# raspi3_nonHat.net
KiCad netlist of a schematic drawn in EAGLE
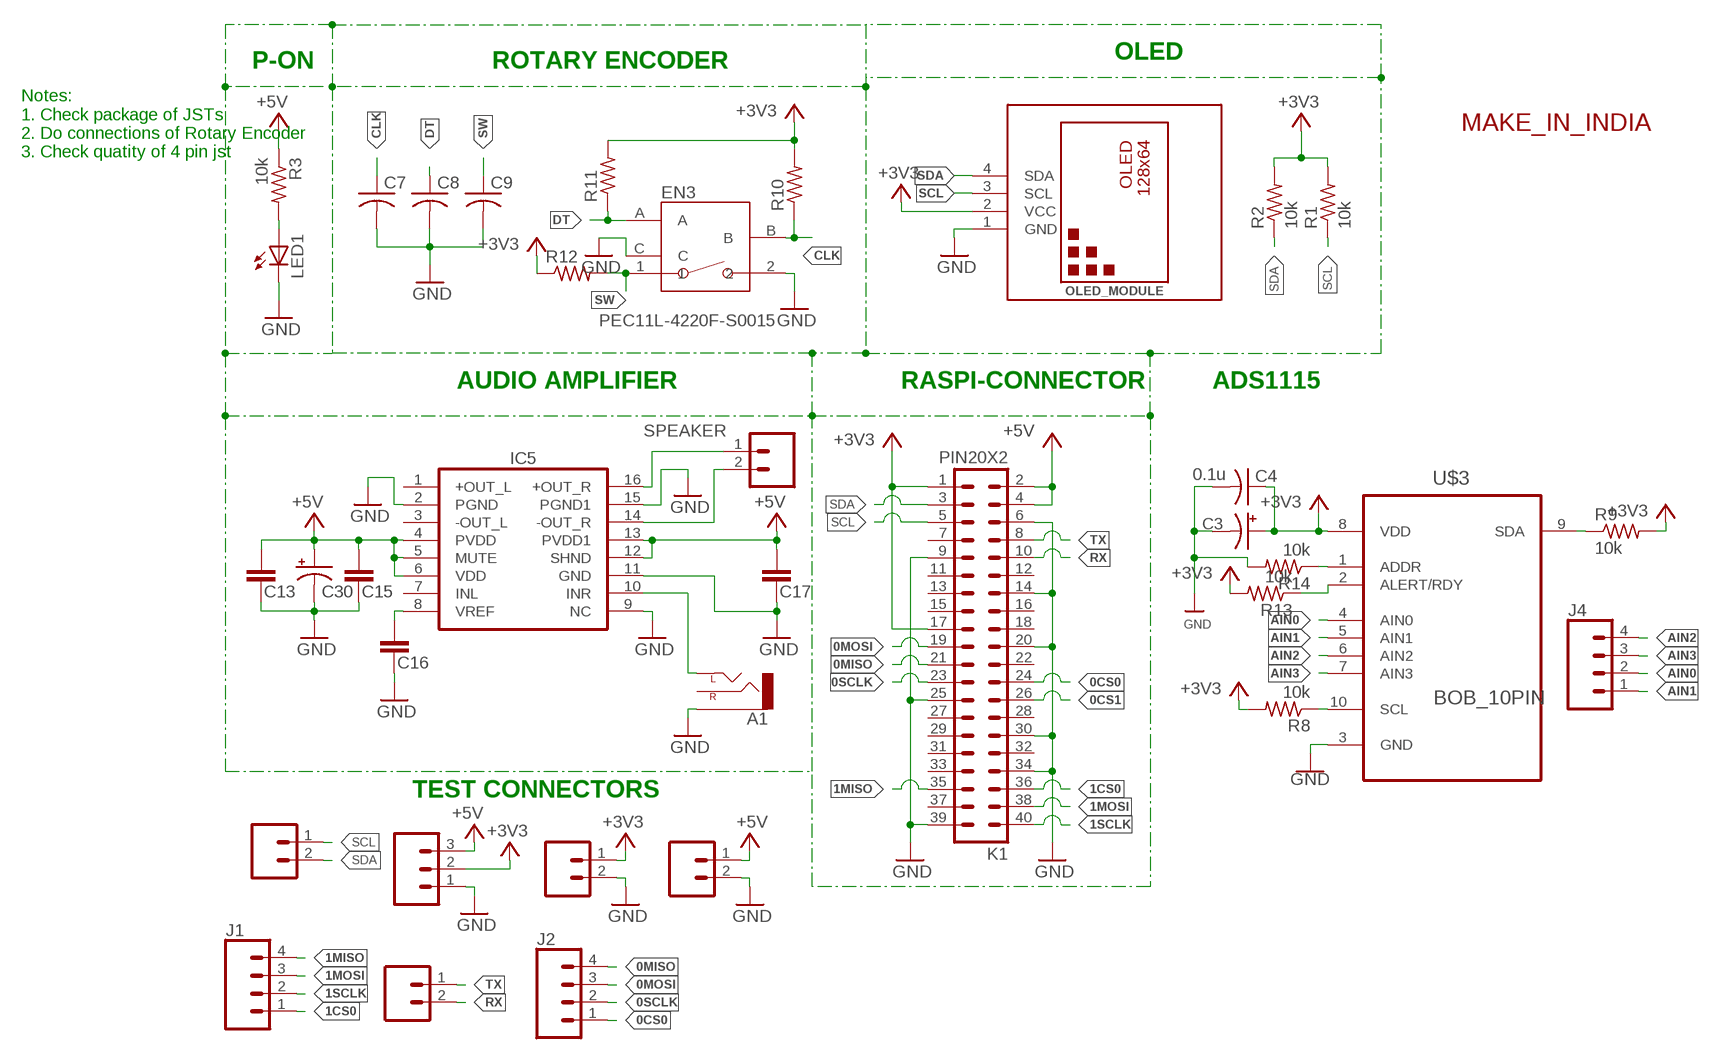
[diagram p0: schematic, sheet 1]

(export (version "E")
  (design (tool "Eeschema 10.0.6"))
  (components
    (comp (ref "A1")
      (value "AUDIO-JACKPTH")
      (footprint "eagle-import:AUDIO-JACK")
      (libsource (lib "eagle-import") (part "AUDIO-JACKPTH"))
    )
    (comp (ref "C3")
      (value "10u")
      (footprint "eagle-import:C_6032-28R")
      (libsource (lib "eagle-import") (part "CAP_POL_10V"))
    )
    (comp (ref "C4")
      (value "0.1u")
      (footprint "eagle-import:C0805")
      (libsource (lib "eagle-import") (part "CAP0805"))
    )
    (comp (ref "C7")
      (value "C-USC0603K")
      (footprint "eagle-import:C0603K")
      (libsource (lib "eagle-import") (part "C-USC0603K"))
    )
    (comp (ref "C8")
      (value "C-USC0603K")
      (footprint "eagle-import:C0603K")
      (libsource (lib "eagle-import") (part "C-USC0603K"))
    )
    (comp (ref "C9")
      (value "C-USC0603K")
      (footprint "eagle-import:C0603K")
      (libsource (lib "eagle-import") (part "C-USC0603K"))
    )
    (comp (ref "C13")
      (value "1uf")
      (footprint "eagle-import:C1206")
      (libsource (lib "eagle-import") (part "C-EUC1206"))
    )
    (comp (ref "C15")
      (value "1uf")
      (footprint "eagle-import:C1206")
      (libsource (lib "eagle-import") (part "C-EUC1206"))
    )
    (comp (ref "C16")
      (value "0.1uf")
      (footprint "eagle-import:C1206")
      (libsource (lib "eagle-import") (part "C-EUC1206"))
    )
    (comp (ref "C17")
      (value "1uf")
      (footprint "eagle-import:C1206")
      (libsource (lib "eagle-import") (part "C-EUC1206"))
    )
    (comp (ref "C30")
      (value "CAP_POL_10V")
      (footprint "eagle-import:C_6032-28R")
      (libsource (lib "eagle-import") (part "CEDT_SEPTEMBER_V2_CAP_POL_10V"))
    )
    (comp (ref "EN3")
      (value "PEC11L-4220F-S0015")
      (footprint "eagle-import:PEC11L-4220F-S0015")
      (fields
        (field (name "DIGIKEY_PARTNO") "PEC11L-4220F-S0015-ND")
        (field (name "MANUFACTURER") "Bourns Inc.")
        (field (name "CREATED_BY") "PCBLayout.com")
      )
      (libsource (lib "eagle-import") (part "PEC11L-4220F-S0015"))
    )
    (comp (ref "IC5")
      (value "PAM8403")
      (footprint "eagle-import:SOP-16")
      (libsource (lib "eagle-import") (part "PAM8403"))
    )
    (comp (ref "J1")
      (value "CONN_04POLAR")
      (footprint "eagle-import:MOLEX-1X4")
      (libsource (lib "eagle-import") (part "CONN_04POLAR"))
    )
    (comp (ref "J2")
      (value "CONN_04POLAR")
      (footprint "eagle-import:MOLEX-1X4")
      (libsource (lib "eagle-import") (part "CONN_04POLAR"))
    )
    (comp (ref "J4")
      (value "CONN_04POLAR")
      (footprint "eagle-import:MOLEX-1X4")
      (libsource (lib "eagle-import") (part "CONN_04POLAR"))
    )
    (comp (ref "K1")
      (value "PIN20X2")
      (footprint "eagle-import:PIN_20X2")
      (libsource (lib "eagle-import") (part "PIN20X2"))
    )
    (comp (ref "LED1")
      (value "LED3MM")
      (footprint "eagle-import:LED3MM")
      (libsource (lib "eagle-import") (part "LED3MM"))
    )
    (comp (ref "OLED_MODULE")
      (value "DIY-MODULES_DISPLAY-OLED-128X64-I2C")
      (footprint "eagle-import:DIY-MODULES_DISPLAY-OLED-128X64-I2C")
      (libsource (lib "eagle-import") (part "DIY-MODULES_DISPLAY-OLED-128X64-I2C"))
    )
    (comp (ref "POWER")
      (value "CONN_03POLAR")
      (footprint "eagle-import:MOLEX-1X3")
      (libsource (lib "eagle-import") (part "CONN_03POLAR"))
    )
    (comp (ref "R1")
      (value "10k")
      (footprint "eagle-import:0207_7")
      (libsource (lib "eagle-import") (part "RESISTOR0207/7"))
    )
    (comp (ref "R2")
      (value "10k")
      (footprint "eagle-import:0207_7")
      (libsource (lib "eagle-import") (part "RESISTOR0207/7"))
    )
    (comp (ref "R3")
      (value "10k")
      (footprint "eagle-import:0207_7")
      (libsource (lib "eagle-import") (part "RESISTOR0207/7"))
    )
    (comp (ref "R8")
      (value "10k")
      (footprint "eagle-import:R0603")
      (libsource (lib "eagle-import") (part "CEDT_JANUARY_2015_v5_RESISTOR0603"))
    )
    (comp (ref "R9")
      (value "10k")
      (footprint "eagle-import:R0603")
      (libsource (lib "eagle-import") (part "CEDT_JANUARY_2015_v5_RESISTOR0603"))
    )
    (comp (ref "R10")
      (value "R-US_M0805")
      (footprint "eagle-import:M0805")
      (libsource (lib "eagle-import") (part "R-US_M0805"))
    )
    (comp (ref "R11")
      (value "R-US_M0805")
      (footprint "eagle-import:M0805")
      (libsource (lib "eagle-import") (part "R-US_M0805"))
    )
    (comp (ref "R12")
      (value "R-US_M0805")
      (footprint "eagle-import:M0805")
      (libsource (lib "eagle-import") (part "R-US_M0805"))
    )
    (comp (ref "R13")
      (value "10k")
      (footprint "eagle-import:R0603")
      (libsource (lib "eagle-import") (part "CEDT_JANUARY_2015_v5_RESISTOR0603"))
    )
    (comp (ref "R14")
      (value "10k")
      (footprint "eagle-import:R0603")
      (libsource (lib "eagle-import") (part "CEDT_JANUARY_2015_v5_RESISTOR0603"))
    )
    (comp (ref "SPEAKER")
      (value "M02")
      (footprint "eagle-import:02P")
      (libsource (lib "eagle-import") (part "M02"))
    )
    (comp (ref "THERMISTOR1")
      (value "CONN_02POLAR")
      (footprint "eagle-import:MOLEX-1X2")
      (libsource (lib "eagle-import") (part "CONN_02POLAR"))
    )
    (comp (ref "THERMISTOR2")
      (value "CONN_02POLAR")
      (footprint "eagle-import:MOLEX-1X2")
      (libsource (lib "eagle-import") (part "CONN_02POLAR"))
    )
    (comp (ref "THERMISTOR3")
      (value "CONN_02POLAR")
      (footprint "eagle-import:MOLEX-1X2")
      (libsource (lib "eagle-import") (part "CONN_02POLAR"))
    )
    (comp (ref "THERMISTOR4")
      (value "CONN_02POLAR")
      (footprint "eagle-import:MOLEX-1X2")
      (libsource (lib "eagle-import") (part "CONN_02POLAR"))
    )
    (comp (ref "U$1")
      (value "MAKE-IN-INDIA-LOGO")
      (footprint "eagle-import:MAKE-IN-INDIA")
      (libsource (lib "eagle-import") (part "MAKE-IN-INDIA-LOGO"))
    )
    (comp (ref "U$3")
      (value "BOB_10PIN")
      (footprint "eagle-import:BOB10")
      (libsource (lib "eagle-import") (part "BOB_10PIN"))
    )
  )
  (nets
    (net (code "1") (name "+3V3") (class "Default")
      (node (ref "C3") (pin "+") (pinfunction "+_+") (pintype "passive"))
      (node (ref "C4") (pin "1") (pinfunction "1_1") (pintype "passive"))
      (node (ref "K1") (pin "1") (pinfunction "1_1") (pintype "passive"))
      (node (ref "K1") (pin "17") (pinfunction "17_17") (pintype "passive"))
      (node (ref "OLED_MODULE") (pin "2") (pinfunction "VCC_2") (pintype "power_in"))
      (node (ref "POWER") (pin "2") (pinfunction "2_2") (pintype "passive"))
      (node (ref "R1") (pin "2") (pinfunction "2_2") (pintype "passive"))
      (node (ref "R10") (pin "2") (pinfunction "2_2") (pintype "passive"))
      (node (ref "R11") (pin "2") (pinfunction "2_2") (pintype "passive"))
      (node (ref "R12") (pin "1") (pinfunction "1_1") (pintype "passive"))
      (node (ref "R13") (pin "2") (pinfunction "2_2") (pintype "passive"))
      (node (ref "R2") (pin "2") (pinfunction "2_2") (pintype "passive"))
      (node (ref "R8") (pin "2") (pinfunction "2_2") (pintype "passive"))
      (node (ref "R9") (pin "2") (pinfunction "2_2") (pintype "passive"))
      (node (ref "THERMISTOR2") (pin "1") (pinfunction "1_1") (pintype "passive"))
      (node (ref "U$3") (pin "8") (pinfunction "VDD_8") (pintype "power_in"))
    )
    (net (code "2") (name "+5V") (class "Default")
      (node (ref "C13") (pin "1") (pinfunction "1_1") (pintype "passive"))
      (node (ref "C15") (pin "2") (pinfunction "2_2") (pintype "passive"))
      (node (ref "C17") (pin "2") (pinfunction "2_2") (pintype "passive"))
      (node (ref "C30") (pin "+") (pinfunction "+_+") (pintype "passive"))
      (node (ref "IC5") (pin "12") (pinfunction "SHND_12") (pintype "output"))
      (node (ref "IC5") (pin "13") (pinfunction "PVDD1_13") (pintype "output"))
      (node (ref "IC5") (pin "4") (pinfunction "PVDD_4") (pintype "input"))
      (node (ref "IC5") (pin "5") (pinfunction "MUTE_5") (pintype "input"))
      (node (ref "IC5") (pin "6") (pinfunction "VDD_6") (pintype "input"))
      (node (ref "K1") (pin "2") (pinfunction "2_2") (pintype "passive"))
      (node (ref "K1") (pin "4") (pinfunction "4_4") (pintype "passive"))
      (node (ref "POWER") (pin "3") (pinfunction "3_3") (pintype "passive"))
      (node (ref "R3") (pin "1") (pinfunction "1_1") (pintype "passive"))
      (node (ref "THERMISTOR3") (pin "1") (pinfunction "1_1") (pintype "passive"))
    )
    (net (code "3") (name "0CS0") (class "Default")
      (node (ref "J2") (pin "1") (pinfunction "1_1") (pintype "passive"))
      (node (ref "K1") (pin "24") (pinfunction "24_24") (pintype "passive"))
    )
    (net (code "4") (name "0CS1") (class "Default")
      (node (ref "K1") (pin "26") (pinfunction "26_26") (pintype "passive"))
    )
    (net (code "5") (name "0MISO") (class "Default")
      (node (ref "J2") (pin "4") (pinfunction "4_4") (pintype "passive"))
      (node (ref "K1") (pin "21") (pinfunction "21_21") (pintype "passive"))
    )
    (net (code "6") (name "0MOSI") (class "Default")
      (node (ref "J2") (pin "3") (pinfunction "3_3") (pintype "passive"))
      (node (ref "K1") (pin "19") (pinfunction "19_19") (pintype "passive"))
    )
    (net (code "7") (name "0SCLK") (class "Default")
      (node (ref "J2") (pin "2") (pinfunction "2_2") (pintype "passive"))
      (node (ref "K1") (pin "23") (pinfunction "23_23") (pintype "passive"))
    )
    (net (code "8") (name "1CS0") (class "Default")
      (node (ref "J1") (pin "1") (pinfunction "1_1") (pintype "passive"))
      (node (ref "K1") (pin "36") (pinfunction "36_36") (pintype "passive"))
    )
    (net (code "9") (name "1MISO") (class "Default")
      (node (ref "J1") (pin "4") (pinfunction "4_4") (pintype "passive"))
      (node (ref "K1") (pin "35") (pinfunction "35_35") (pintype "passive"))
    )
    (net (code "10") (name "1MOSI") (class "Default")
      (node (ref "J1") (pin "3") (pinfunction "3_3") (pintype "passive"))
      (node (ref "K1") (pin "38") (pinfunction "38_38") (pintype "passive"))
    )
    (net (code "11") (name "1SCLK") (class "Default")
      (node (ref "J1") (pin "2") (pinfunction "2_2") (pintype "passive"))
      (node (ref "K1") (pin "40") (pinfunction "40_40") (pintype "passive"))
    )
    (net (code "12") (name "AIN0") (class "Default")
      (node (ref "J4") (pin "2") (pinfunction "2_2") (pintype "passive"))
      (node (ref "U$3") (pin "4") (pinfunction "AIN0_4") (pintype "input"))
    )
    (net (code "13") (name "AIN1") (class "Default")
      (node (ref "J4") (pin "1") (pinfunction "1_1") (pintype "passive"))
      (node (ref "U$3") (pin "5") (pinfunction "AIN1_5") (pintype "input"))
    )
    (net (code "14") (name "AIN2") (class "Default")
      (node (ref "J4") (pin "4") (pinfunction "4_4") (pintype "passive"))
      (node (ref "U$3") (pin "6") (pinfunction "AIN2_6") (pintype "input"))
    )
    (net (code "15") (name "AIN3") (class "Default")
      (node (ref "J4") (pin "3") (pinfunction "3_3") (pintype "passive"))
      (node (ref "U$3") (pin "7") (pinfunction "AIN3_7") (pintype "input"))
    )
    (net (code "16") (name "CLK") (class "Default")
      (node (ref "C7") (pin "1") (pinfunction "1_1") (pintype "passive"))
      (node (ref "EN3") (pin "B") (pinfunction "B_B") (pintype "passive"))
      (node (ref "R10") (pin "1") (pinfunction "1_1") (pintype "passive"))
    )
    (net (code "17") (name "DT") (class "Default")
      (node (ref "C8") (pin "1") (pinfunction "1_1") (pintype "passive"))
      (node (ref "EN3") (pin "A") (pinfunction "A_A") (pintype "passive"))
      (node (ref "R11") (pin "1") (pinfunction "1_1") (pintype "passive"))
    )
    (net (code "18") (name "GND") (class "Default")
      (node (ref "A1") (pin "SLEEVE") (pinfunction "SLEEVE_SLEEVE") (pintype "bidirectional"))
      (node (ref "C13") (pin "2") (pinfunction "2_2") (pintype "passive"))
      (node (ref "C15") (pin "1") (pinfunction "1_1") (pintype "passive"))
      (node (ref "C16") (pin "2") (pinfunction "2_2") (pintype "passive"))
      (node (ref "C17") (pin "1") (pinfunction "1_1") (pintype "passive"))
      (node (ref "C3") (pin "-") (pinfunction "-_-") (pintype "passive"))
      (node (ref "C30") (pin "-") (pinfunction "-_-") (pintype "passive"))
      (node (ref "C4") (pin "2") (pinfunction "2_2") (pintype "passive"))
      (node (ref "C7") (pin "2") (pinfunction "2_2") (pintype "passive"))
      (node (ref "C8") (pin "2") (pinfunction "2_2") (pintype "passive"))
      (node (ref "C9") (pin "2") (pinfunction "2_2") (pintype "passive"))
      (node (ref "EN3") (pin "2") (pinfunction "2_2") (pintype "passive"))
      (node (ref "EN3") (pin "C") (pinfunction "C_C") (pintype "passive"))
      (node (ref "IC5") (pin "11") (pinfunction "GND_11") (pintype "output"))
      (node (ref "IC5") (pin "15") (pinfunction "PGND1_15") (pintype "output"))
      (node (ref "IC5") (pin "2") (pinfunction "PGND_2") (pintype "input"))
      (node (ref "IC5") (pin "9") (pinfunction "NC_9") (pintype "output"))
      (node (ref "K1") (pin "14") (pinfunction "14_14") (pintype "passive"))
      (node (ref "K1") (pin "20") (pinfunction "20_20") (pintype "passive"))
      (node (ref "K1") (pin "25") (pinfunction "25_25") (pintype "passive"))
      (node (ref "K1") (pin "30") (pinfunction "30_30") (pintype "passive"))
      (node (ref "K1") (pin "34") (pinfunction "34_34") (pintype "passive"))
      (node (ref "K1") (pin "39") (pinfunction "39_39") (pintype "passive"))
      (node (ref "K1") (pin "6") (pinfunction "6_6") (pintype "passive"))
      (node (ref "K1") (pin "9") (pinfunction "9_9") (pintype "passive"))
      (node (ref "LED1") (pin "K") (pinfunction "C_K") (pintype "passive"))
      (node (ref "OLED_MODULE") (pin "1") (pinfunction "GND_1") (pintype "power_in"))
      (node (ref "POWER") (pin "1") (pinfunction "1_1") (pintype "passive"))
      (node (ref "R14") (pin "2") (pinfunction "2_2") (pintype "passive"))
      (node (ref "THERMISTOR2") (pin "2") (pinfunction "2_2") (pintype "passive"))
      (node (ref "THERMISTOR3") (pin "2") (pinfunction "2_2") (pintype "passive"))
      (node (ref "U$3") (pin "3") (pinfunction "GND_3") (pintype "passive"))
    )
    (net (code "19") (name "Net-(A1-LEFT)") (class "Default")
      (node (ref "A1") (pin "TIP") (pinfunction "LEFT_TIP") (pintype "bidirectional"))
      (node (ref "IC5") (pin "10") (pinfunction "INR_10") (pintype "output"))
    )
    (net (code "20") (name "Net-(IC5-+OUT_R)") (class "Default")
      (node (ref "IC5") (pin "16") (pinfunction "+OUT_R_16") (pintype "output"))
      (node (ref "SPEAKER") (pin "1") (pinfunction "1_1") (pintype "passive"))
    )
    (net (code "21") (name "Net-(IC5--OUT_R)") (class "Default")
      (node (ref "IC5") (pin "14") (pinfunction "-OUT_R_14") (pintype "output"))
      (node (ref "SPEAKER") (pin "2") (pinfunction "2_2") (pintype "passive"))
    )
    (net (code "22") (name "Net-(IC5-VREF)") (class "Default")
      (node (ref "C16") (pin "1") (pinfunction "1_1") (pintype "passive"))
      (node (ref "IC5") (pin "8") (pinfunction "VREF_8") (pintype "input"))
    )
    (net (code "23") (name "Net-(LED1-PadA)") (class "Default")
      (node (ref "LED1") (pin "A") (pinfunction "A_A") (pintype "passive"))
      (node (ref "R3") (pin "2") (pinfunction "2_2") (pintype "passive"))
    )
    (net (code "24") (name "Net-(U$3-ADDR)") (class "Default")
      (node (ref "R14") (pin "1") (pinfunction "1_1") (pintype "passive"))
      (node (ref "U$3") (pin "1") (pinfunction "ADDR_1") (pintype "input"))
    )
    (net (code "25") (name "Net-(U$3-ALERT{slash}RDY)") (class "Default")
      (node (ref "R13") (pin "1") (pinfunction "1_1") (pintype "passive"))
      (node (ref "U$3") (pin "2") (pinfunction "ALERT/RDY_2") (pintype "input"))
    )
    (net (code "26") (name "Net-(U$3-SCL)") (class "Default")
      (node (ref "R8") (pin "1") (pinfunction "1_1") (pintype "passive"))
      (node (ref "U$3") (pin "10") (pinfunction "SCL_10") (pintype "input"))
    )
    (net (code "27") (name "Net-(U$3-SDA)") (class "Default")
      (node (ref "R9") (pin "1") (pinfunction "1_1") (pintype "passive"))
      (node (ref "U$3") (pin "9") (pinfunction "SDA_9") (pintype "bidirectional"))
    )
    (net (code "28") (name "RX") (class "Default")
      (node (ref "K1") (pin "10") (pinfunction "10_10") (pintype "passive"))
      (node (ref "THERMISTOR4") (pin "2") (pinfunction "2_2") (pintype "passive"))
    )
    (net (code "29") (name "SCL") (class "Default")
      (node (ref "K1") (pin "5") (pinfunction "5_5") (pintype "passive"))
      (node (ref "OLED_MODULE") (pin "3") (pinfunction "SCL_3") (pintype "bidirectional"))
      (node (ref "R1") (pin "1") (pinfunction "1_1") (pintype "passive"))
      (node (ref "THERMISTOR1") (pin "1") (pinfunction "1_1") (pintype "passive"))
    )
    (net (code "30") (name "SDA") (class "Default")
      (node (ref "K1") (pin "3") (pinfunction "3_3") (pintype "passive"))
      (node (ref "OLED_MODULE") (pin "4") (pinfunction "SDA_4") (pintype "bidirectional"))
      (node (ref "R2") (pin "1") (pinfunction "1_1") (pintype "passive"))
      (node (ref "THERMISTOR1") (pin "2") (pinfunction "2_2") (pintype "passive"))
    )
    (net (code "31") (name "SW") (class "Default")
      (node (ref "C9") (pin "1") (pinfunction "1_1") (pintype "passive"))
      (node (ref "EN3") (pin "1") (pinfunction "1_1") (pintype "passive"))
      (node (ref "R12") (pin "2") (pinfunction "2_2") (pintype "passive"))
    )
    (net (code "32") (name "TX") (class "Default")
      (node (ref "K1") (pin "8") (pinfunction "8_8") (pintype "passive"))
      (node (ref "THERMISTOR4") (pin "1") (pinfunction "1_1") (pintype "passive"))
    )
    (net (code "33") (name "unconnected-(A1-RIGHT-PadRING)") (class "Default")
      (node (ref "A1") (pin "RING") (pinfunction "RIGHT_RING") (pintype "bidirectional"))
    )
    (net (code "34") (name "unconnected-(IC5-+OUT_L-Pad1)") (class "Default")
      (node (ref "IC5") (pin "1") (pinfunction "+OUT_L_1") (pintype "input"))
    )
    (net (code "35") (name "unconnected-(IC5--OUT_L-Pad3)") (class "Default")
      (node (ref "IC5") (pin "3") (pinfunction "-OUT_L_3") (pintype "input"))
    )
    (net (code "36") (name "unconnected-(IC5-INL-Pad7)") (class "Default")
      (node (ref "IC5") (pin "7") (pinfunction "INL_7") (pintype "input"))
    )
    (net (code "37") (name "unconnected-(K1-Pad7)") (class "Default")
      (node (ref "K1") (pin "7") (pinfunction "7_7") (pintype "passive"))
    )
    (net (code "38") (name "unconnected-(K1-Pad11)") (class "Default")
      (node (ref "K1") (pin "11") (pinfunction "11_11") (pintype "passive"))
    )
    (net (code "39") (name "unconnected-(K1-Pad12)") (class "Default")
      (node (ref "K1") (pin "12") (pinfunction "12_12") (pintype "passive"))
    )
    (net (code "40") (name "unconnected-(K1-Pad13)") (class "Default")
      (node (ref "K1") (pin "13") (pinfunction "13_13") (pintype "passive"))
    )
    (net (code "41") (name "unconnected-(K1-Pad15)") (class "Default")
      (node (ref "K1") (pin "15") (pinfunction "15_15") (pintype "passive"))
    )
    (net (code "42") (name "unconnected-(K1-Pad16)") (class "Default")
      (node (ref "K1") (pin "16") (pinfunction "16_16") (pintype "passive"))
    )
    (net (code "43") (name "unconnected-(K1-Pad18)") (class "Default")
      (node (ref "K1") (pin "18") (pinfunction "18_18") (pintype "passive"))
    )
    (net (code "44") (name "unconnected-(K1-Pad22)") (class "Default")
      (node (ref "K1") (pin "22") (pinfunction "22_22") (pintype "passive"))
    )
    (net (code "45") (name "unconnected-(K1-Pad27)") (class "Default")
      (node (ref "K1") (pin "27") (pinfunction "27_27") (pintype "passive"))
    )
    (net (code "46") (name "unconnected-(K1-Pad28)") (class "Default")
      (node (ref "K1") (pin "28") (pinfunction "28_28") (pintype "passive"))
    )
    (net (code "47") (name "unconnected-(K1-Pad29)") (class "Default")
      (node (ref "K1") (pin "29") (pinfunction "29_29") (pintype "passive"))
    )
    (net (code "48") (name "unconnected-(K1-Pad31)") (class "Default")
      (node (ref "K1") (pin "31") (pinfunction "31_31") (pintype "passive"))
    )
    (net (code "49") (name "unconnected-(K1-Pad32)") (class "Default")
      (node (ref "K1") (pin "32") (pinfunction "32_32") (pintype "passive"))
    )
    (net (code "50") (name "unconnected-(K1-Pad33)") (class "Default")
      (node (ref "K1") (pin "33") (pinfunction "33_33") (pintype "passive"))
    )
    (net (code "51") (name "unconnected-(K1-Pad37)") (class "Default")
      (node (ref "K1") (pin "37") (pinfunction "37_37") (pintype "passive"))
    )
  )
)
